# Regulator.net
KiCad netlist of a schematic drawn in Altium Designer
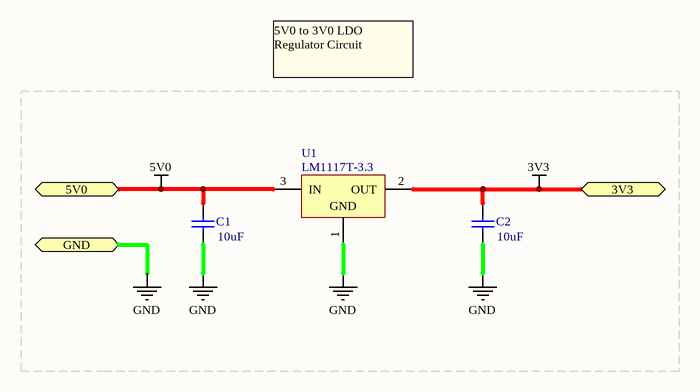
[diagram p0: Regulator.SchDoc]

(export (version "E")
  (design (tool "Eeschema 10.0.6"))
  (components
    (comp (ref "C1")
      (value "10uF")
      (footprint "RAD-0.3")
      (description "Capacitor")
      (fields (field (name "Comment") "Cap") (field (name "PUBLISHER") "Altium Limited"))
      (libsource (lib "Miscellaneous Devices") (part "Cap"))
    )
    (comp (ref "C2")
      (value "10uF")
      (footprint "RAD-0.3")
      (description "Capacitor")
      (fields (field (name "Comment") "Cap") (field (name "PUBLISHER") "Altium Limited"))
      (libsource (lib "Miscellaneous Devices") (part "Cap"))
    )
    (comp (ref "U1")
      (value "LM1117T-3.3")
      (footprint "T03B")
      (description "800mA Low-Dropout Linear Regulator, 3-pin TO-220")
      (fields (field (name "MANUFACTURER") "National Semiconductor"))
      (libsource (lib "Altium Content Vault") (part "PM-REG-LM1086-SIL3"))
    )
  )
  (nets
    (net (code "1") (name "3V3") (class "Default")
      (node (ref "C2") (pin "2") (pinfunction "2_2") (pintype "passive"))
      (node (ref "U1") (pin "2") (pinfunction "OUT_2") (pintype "power_in"))
    )
    (net (code "2") (name "5V0") (class "Default")
      (node (ref "C1") (pin "2") (pinfunction "2_2") (pintype "passive"))
      (node (ref "U1") (pin "3") (pinfunction "IN_3") (pintype "power_in"))
    )
    (net (code "3") (name "GND") (class "Default")
      (node (ref "C1") (pin "1") (pinfunction "1_1") (pintype "passive"))
      (node (ref "C2") (pin "1") (pinfunction "1_1") (pintype "passive"))
      (node (ref "U1") (pin "1") (pinfunction "GND_1") (pintype "power_in"))
    )
  )
)
